# Rotator.net
KiCad netlist of a schematic drawn in EAGLE
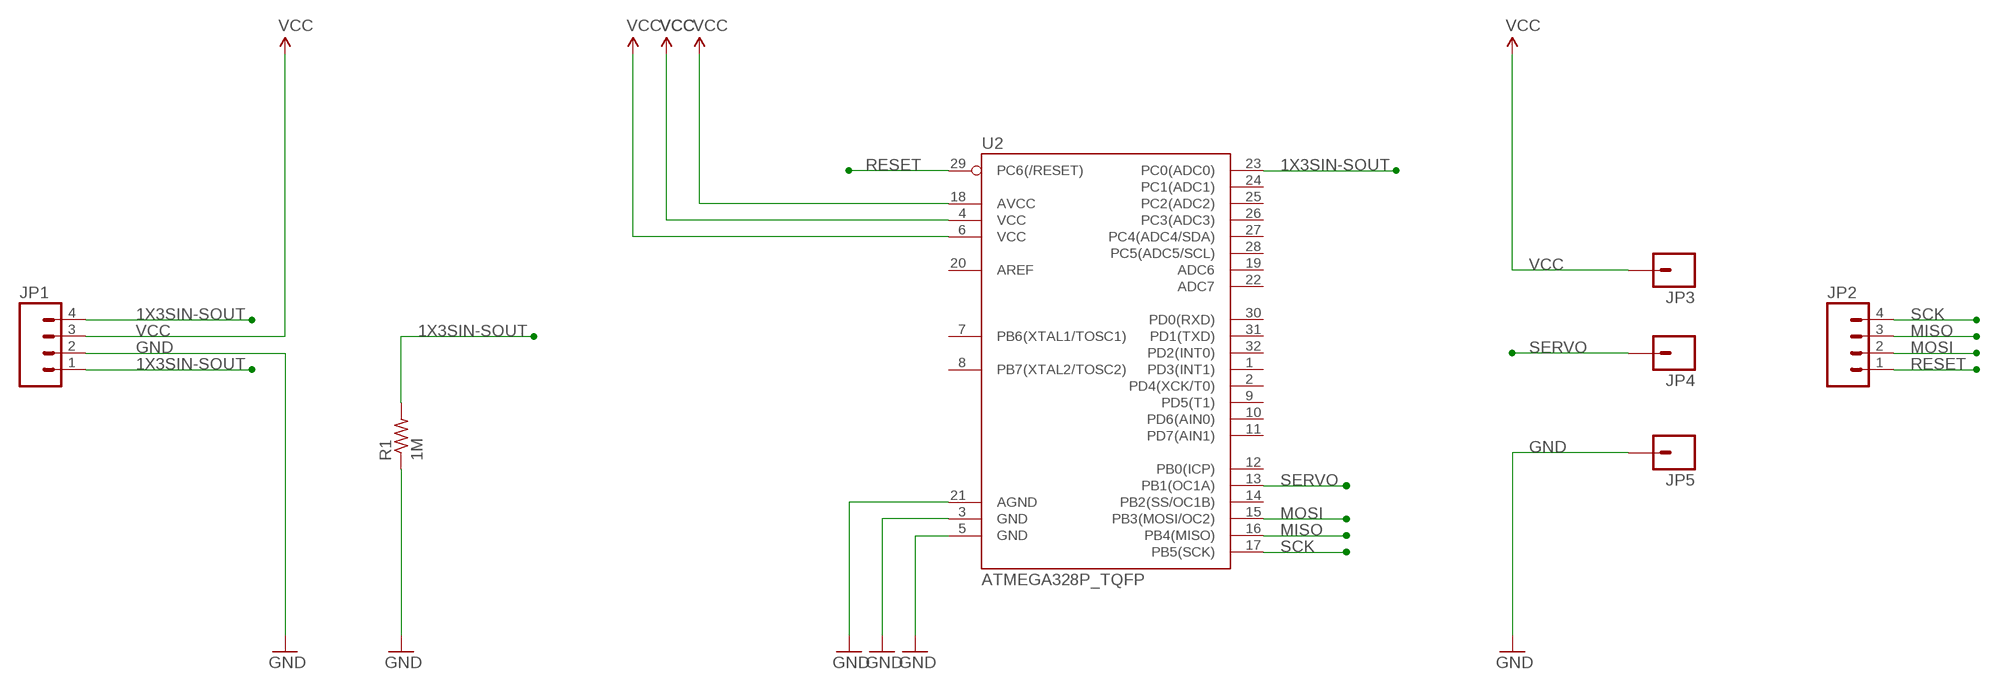
[diagram p0: schematic, sheet 1]

(export (version "E")
  (design (tool "Eeschema 10.0.6"))
  (components
    (comp (ref "JP1")
      (value "M04PTH")
      (footprint "eagle-import:1X04")
      (libsource (lib "eagle-import") (part "M04PTH"))
    )
    (comp (ref "JP2")
      (value "M04PTH")
      (footprint "eagle-import:1X04")
      (libsource (lib "eagle-import") (part "M04PTH"))
    )
    (comp (ref "JP3")
      (value "M01PTH")
      (footprint "eagle-import:1X01")
      (libsource (lib "eagle-import") (part "M01PTH"))
    )
    (comp (ref "JP4")
      (value "M01PTH")
      (footprint "eagle-import:1X01")
      (libsource (lib "eagle-import") (part "M01PTH"))
    )
    (comp (ref "JP5")
      (value "M01PTH")
      (footprint "eagle-import:1X01")
      (libsource (lib "eagle-import") (part "M01PTH"))
    )
    (comp (ref "R1")
      (value "1M")
      (footprint "eagle-import:R0603")
      (libsource (lib "eagle-import") (part "R-US_R0603"))
    )
    (comp (ref "U2")
      (value "ATMEGA328P_TQFP")
      (footprint "eagle-import:TQFP32-08")
      (libsource (lib "eagle-import") (part "ATMEGA328P_TQFP"))
    )
  )
  (nets
    (net (code "1") (name "/1X3SIN-SOUT") (class "Default")
      (node (ref "JP1") (pin "1") (pinfunction "1_1") (pintype "passive"))
      (node (ref "JP1") (pin "4") (pinfunction "4_4") (pintype "passive"))
      (node (ref "R1") (pin "2") (pinfunction "2_2") (pintype "passive"))
      (node (ref "U2") (pin "23") (pinfunction "PC0(ADC0)_23") (pintype "bidirectional"))
    )
    (net (code "2") (name "/MISO") (class "Default")
      (node (ref "JP2") (pin "3") (pinfunction "3_3") (pintype "passive"))
      (node (ref "U2") (pin "16") (pinfunction "PB4(MISO)_16") (pintype "bidirectional"))
    )
    (net (code "3") (name "/MOSI") (class "Default")
      (node (ref "JP2") (pin "2") (pinfunction "2_2") (pintype "passive"))
      (node (ref "U2") (pin "15") (pinfunction "PB3(MOSI/OC2)_15") (pintype "bidirectional"))
    )
    (net (code "4") (name "/RESET") (class "Default")
      (node (ref "JP2") (pin "1") (pinfunction "1_1") (pintype "passive"))
      (node (ref "U2") (pin "29") (pinfunction "PC6(/RESET)_29") (pintype "bidirectional"))
    )
    (net (code "5") (name "/SCK") (class "Default")
      (node (ref "JP2") (pin "4") (pinfunction "4_4") (pintype "passive"))
      (node (ref "U2") (pin "17") (pinfunction "PB5(SCK)_17") (pintype "bidirectional"))
    )
    (net (code "6") (name "/SERVO") (class "Default")
      (node (ref "JP4") (pin "1") (pinfunction "1_1") (pintype "passive"))
      (node (ref "U2") (pin "13") (pinfunction "PB1(OC1A)_13") (pintype "bidirectional"))
    )
    (net (code "7") (name "GND") (class "Default")
      (node (ref "JP1") (pin "2") (pinfunction "2_2") (pintype "passive"))
      (node (ref "JP5") (pin "1") (pinfunction "1_1") (pintype "passive"))
      (node (ref "R1") (pin "1") (pinfunction "1_1") (pintype "passive"))
      (node (ref "U2") (pin "21") (pinfunction "AGND_21") (pintype "bidirectional"))
      (node (ref "U2") (pin "3") (pinfunction "GND_3") (pintype "bidirectional"))
      (node (ref "U2") (pin "5") (pinfunction "GND_5") (pintype "bidirectional"))
    )
    (net (code "8") (name "VCC") (class "Default")
      (node (ref "JP1") (pin "3") (pinfunction "3_3") (pintype "passive"))
      (node (ref "JP3") (pin "1") (pinfunction "1_1") (pintype "passive"))
      (node (ref "U2") (pin "18") (pinfunction "AVCC_18") (pintype "bidirectional"))
      (node (ref "U2") (pin "4") (pinfunction "VCC_4") (pintype "bidirectional"))
      (node (ref "U2") (pin "6") (pinfunction "VCC_6") (pintype "bidirectional"))
    )
    (net (code "9") (name "unconnected-(U2-ADC6-Pad19)") (class "Default")
      (node (ref "U2") (pin "19") (pinfunction "ADC6_19") (pintype "bidirectional"))
    )
    (net (code "10") (name "unconnected-(U2-ADC7-Pad22)") (class "Default")
      (node (ref "U2") (pin "22") (pinfunction "ADC7_22") (pintype "bidirectional"))
    )
    (net (code "11") (name "unconnected-(U2-AREF-Pad20)") (class "Default")
      (node (ref "U2") (pin "20") (pinfunction "AREF_20") (pintype "bidirectional"))
    )
    (net (code "12") (name "unconnected-(U2-PB0(ICP)-Pad12)") (class "Default")
      (node (ref "U2") (pin "12") (pinfunction "PB0(ICP)_12") (pintype "bidirectional"))
    )
    (net (code "13") (name "unconnected-(U2-PB2(SS{slash}OC1B)-Pad14)") (class "Default")
      (node (ref "U2") (pin "14") (pinfunction "PB2(SS/OC1B)_14") (pintype "bidirectional"))
    )
    (net (code "14") (name "unconnected-(U2-PB6(XTAL1{slash}TOSC1)-Pad7)") (class "Default")
      (node (ref "U2") (pin "7") (pinfunction "PB6(XTAL1/TOSC1)_7") (pintype "bidirectional"))
    )
    (net (code "15") (name "unconnected-(U2-PB7(XTAL2{slash}TOSC2)-Pad8)") (class "Default")
      (node (ref "U2") (pin "8") (pinfunction "PB7(XTAL2/TOSC2)_8") (pintype "bidirectional"))
    )
    (net (code "16") (name "unconnected-(U2-PC1(ADC1)-Pad24)") (class "Default")
      (node (ref "U2") (pin "24") (pinfunction "PC1(ADC1)_24") (pintype "bidirectional"))
    )
    (net (code "17") (name "unconnected-(U2-PC2(ADC2)-Pad25)") (class "Default")
      (node (ref "U2") (pin "25") (pinfunction "PC2(ADC2)_25") (pintype "bidirectional"))
    )
    (net (code "18") (name "unconnected-(U2-PC3(ADC3)-Pad26)") (class "Default")
      (node (ref "U2") (pin "26") (pinfunction "PC3(ADC3)_26") (pintype "bidirectional"))
    )
    (net (code "19") (name "unconnected-(U2-PC4(ADC4{slash}SDA)-Pad27)") (class "Default")
      (node (ref "U2") (pin "27") (pinfunction "PC4(ADC4/SDA)_27") (pintype "bidirectional"))
    )
    (net (code "20") (name "unconnected-(U2-PC5(ADC5{slash}SCL)-Pad28)") (class "Default")
      (node (ref "U2") (pin "28") (pinfunction "PC5(ADC5/SCL)_28") (pintype "bidirectional"))
    )
    (net (code "21") (name "unconnected-(U2-PD0(RXD)-Pad30)") (class "Default")
      (node (ref "U2") (pin "30") (pinfunction "PD0(RXD)_30") (pintype "bidirectional"))
    )
    (net (code "22") (name "unconnected-(U2-PD1(TXD)-Pad31)") (class "Default")
      (node (ref "U2") (pin "31") (pinfunction "PD1(TXD)_31") (pintype "bidirectional"))
    )
    (net (code "23") (name "unconnected-(U2-PD2(INT0)-Pad32)") (class "Default")
      (node (ref "U2") (pin "32") (pinfunction "PD2(INT0)_32") (pintype "bidirectional"))
    )
    (net (code "24") (name "unconnected-(U2-PD3(INT1)-Pad1)") (class "Default")
      (node (ref "U2") (pin "1") (pinfunction "PD3(INT1)_1") (pintype "bidirectional"))
    )
    (net (code "25") (name "unconnected-(U2-PD4(XCK{slash}T0)-Pad2)") (class "Default")
      (node (ref "U2") (pin "2") (pinfunction "PD4(XCK/T0)_2") (pintype "bidirectional"))
    )
    (net (code "26") (name "unconnected-(U2-PD5(T1)-Pad9)") (class "Default")
      (node (ref "U2") (pin "9") (pinfunction "PD5(T1)_9") (pintype "bidirectional"))
    )
    (net (code "27") (name "unconnected-(U2-PD6(AIN0)-Pad10)") (class "Default")
      (node (ref "U2") (pin "10") (pinfunction "PD6(AIN0)_10") (pintype "bidirectional"))
    )
    (net (code "28") (name "unconnected-(U2-PD7(AIN1)-Pad11)") (class "Default")
      (node (ref "U2") (pin "11") (pinfunction "PD7(AIN1)_11") (pintype "bidirectional"))
    )
  )
)
